# mecanum_car_controller.net
KiCad netlist of a schematic drawn in Altium Designer
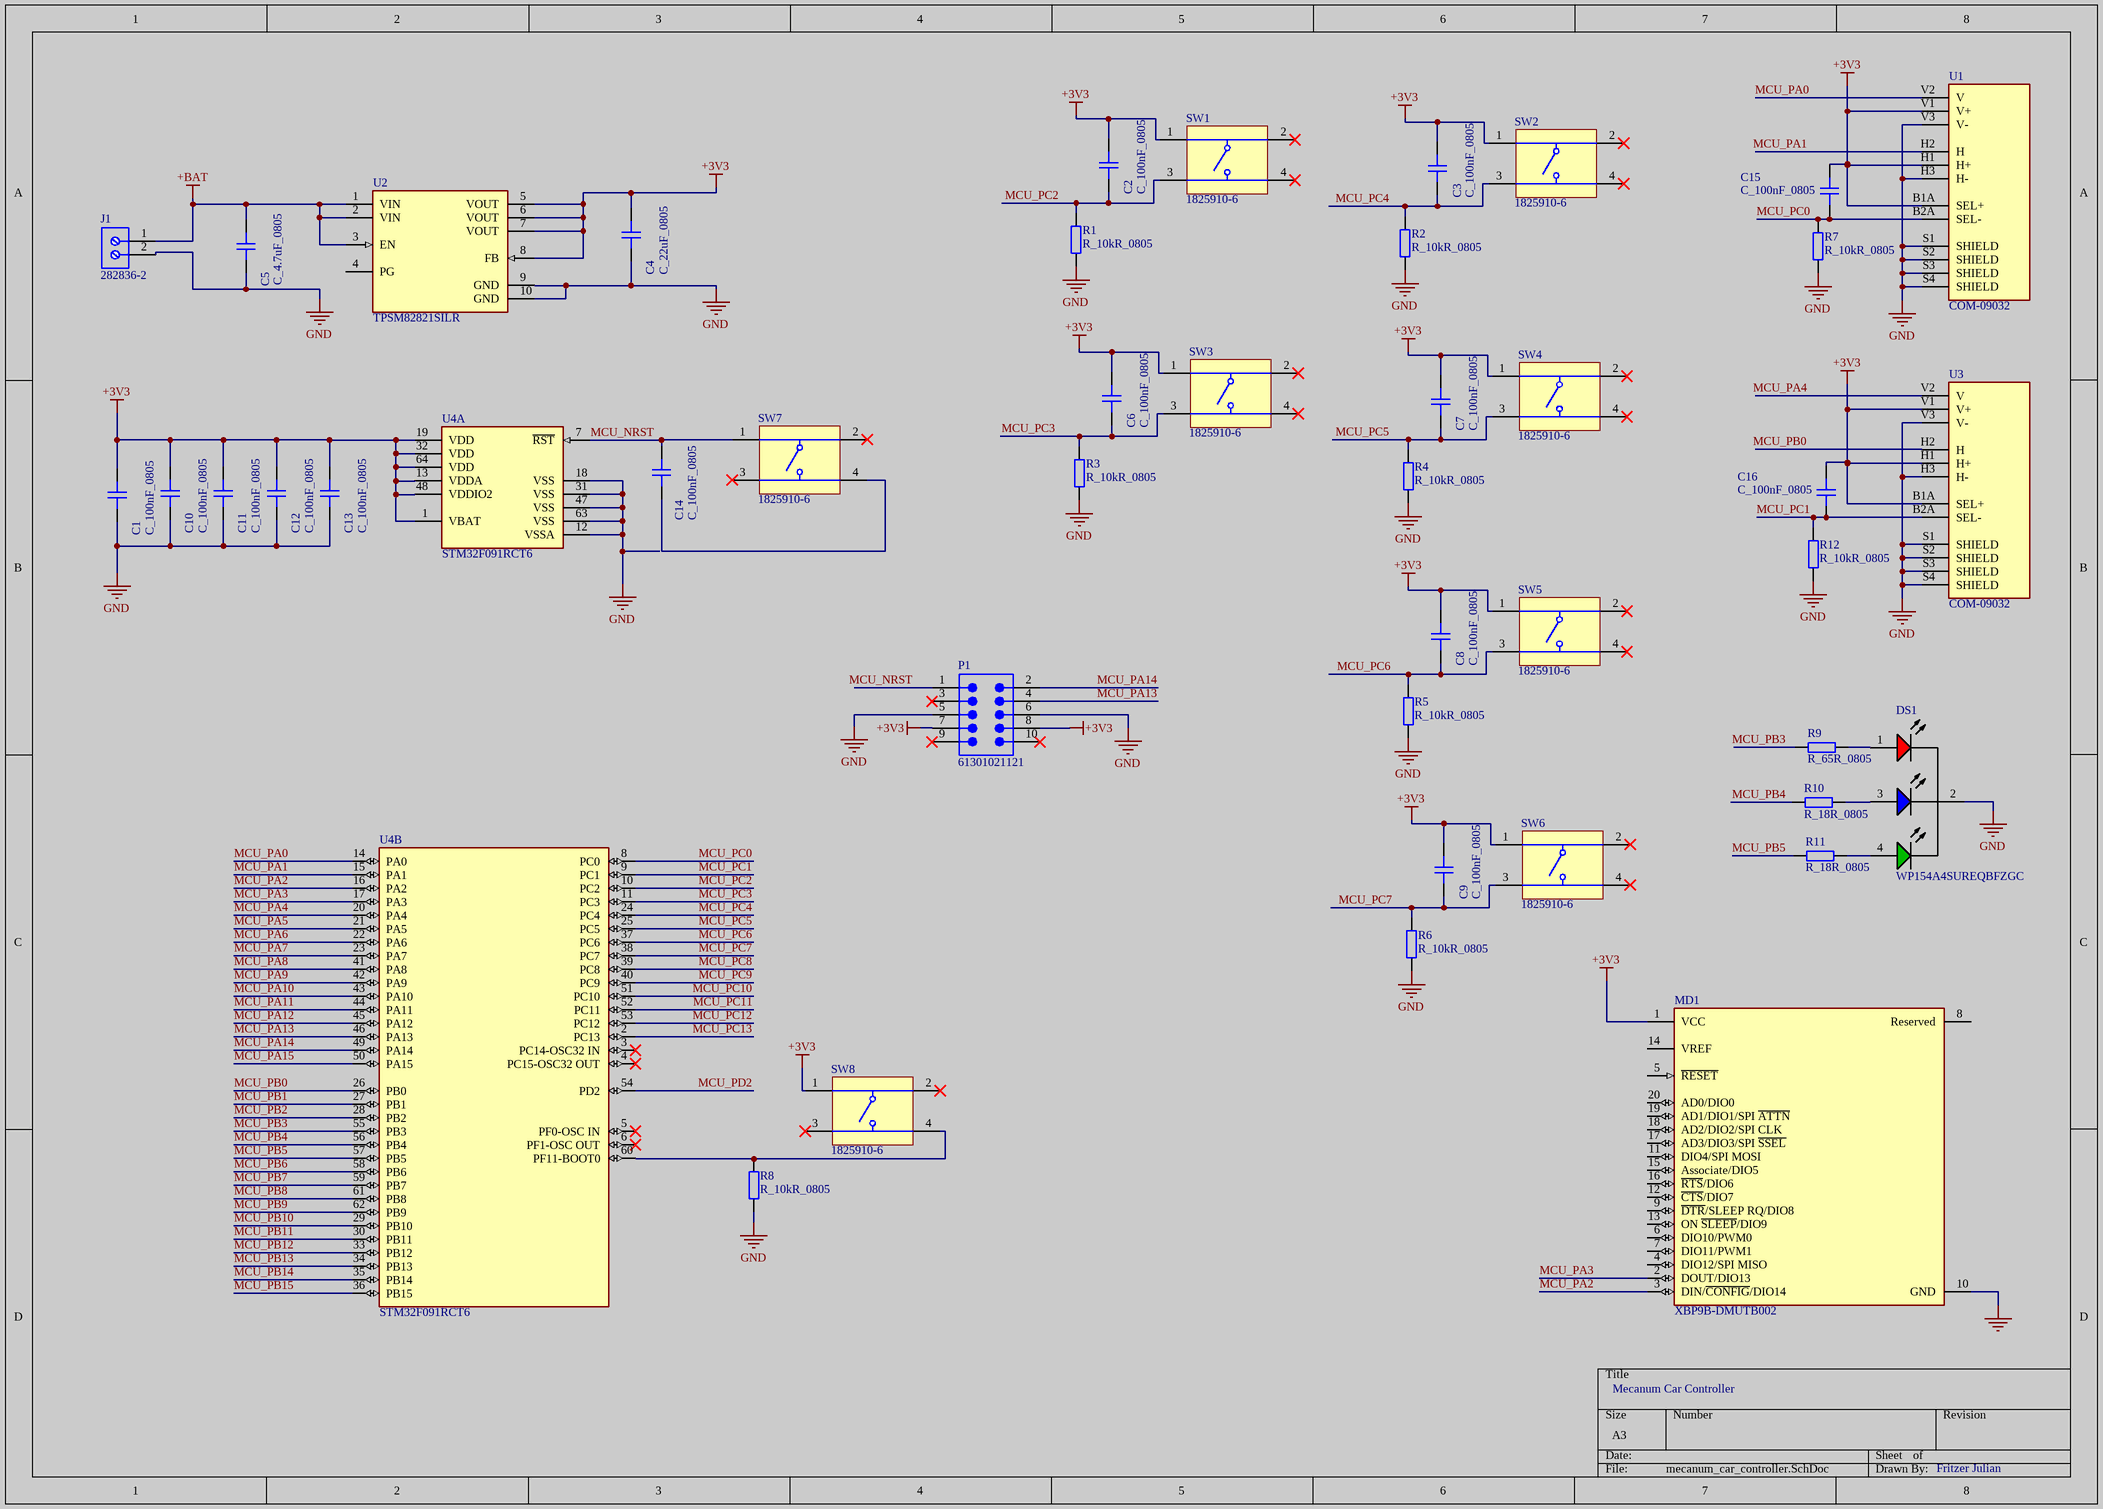
[diagram p0: mecanum_car_controller.SchDoc]

(export (version "E")
  (design (tool "Eeschema 10.0.6"))
  (components
    (comp (ref "C1")
      (value "C_100nF_0805")
      (footprint "CAP_0805")
      (description "Capacitor SMD 0805")
      (libsource (lib "Schematic-Lib-PhilsLab") (part "CAP_0805"))
    )
    (comp (ref "C2")
      (value "C_100nF_0805")
      (footprint "CAP_0805")
      (description "Capacitor SMD 0805")
      (libsource (lib "Schematic-Lib-PhilsLab") (part "CAP_0805"))
    )
    (comp (ref "C3")
      (value "C_100nF_0805")
      (footprint "CAP_0805")
      (description "Capacitor SMD 0805")
      (libsource (lib "Schematic-Lib-PhilsLab") (part "CAP_0805"))
    )
    (comp (ref "C4")
      (value "C_22uF_0805")
      (footprint "CAP_0805")
      (description "Capacitor SMD 0805")
      (libsource (lib "Schematic-Lib-PhilsLab") (part "CAP_0805"))
    )
    (comp (ref "C5")
      (value "C_4.7uF_0805")
      (footprint "CAP_0805")
      (description "Capacitor SMD 0805")
      (libsource (lib "Schematic-Lib-PhilsLab") (part "CAP_0805"))
    )
    (comp (ref "C6")
      (value "C_100nF_0805")
      (footprint "CAP_0805")
      (description "Capacitor SMD 0805")
      (libsource (lib "Schematic-Lib-PhilsLab") (part "CAP_0805"))
    )
    (comp (ref "C7")
      (value "C_100nF_0805")
      (footprint "CAP_0805")
      (description "Capacitor SMD 0805")
      (libsource (lib "Schematic-Lib-PhilsLab") (part "CAP_0805"))
    )
    (comp (ref "C8")
      (value "C_100nF_0805")
      (footprint "CAP_0805")
      (description "Capacitor SMD 0805")
      (libsource (lib "Schematic-Lib-PhilsLab") (part "CAP_0805"))
    )
    (comp (ref "C9")
      (value "C_100nF_0805")
      (footprint "CAP_0805")
      (description "Capacitor SMD 0805")
      (libsource (lib "Schematic-Lib-PhilsLab") (part "CAP_0805"))
    )
    (comp (ref "C10")
      (value "C_100nF_0805")
      (footprint "CAP_0805")
      (description "Capacitor SMD 0805")
      (libsource (lib "Schematic-Lib-PhilsLab") (part "CAP_0805"))
    )
    (comp (ref "C11")
      (value "C_100nF_0805")
      (footprint "CAP_0805")
      (description "Capacitor SMD 0805")
      (libsource (lib "Schematic-Lib-PhilsLab") (part "CAP_0805"))
    )
    (comp (ref "C12")
      (value "C_100nF_0805")
      (footprint "CAP_0805")
      (description "Capacitor SMD 0805")
      (libsource (lib "Schematic-Lib-PhilsLab") (part "CAP_0805"))
    )
    (comp (ref "C13")
      (value "C_100nF_0805")
      (footprint "CAP_0805")
      (description "Capacitor SMD 0805")
      (libsource (lib "Schematic-Lib-PhilsLab") (part "CAP_0805"))
    )
    (comp (ref "C14")
      (value "C_100nF_0805")
      (footprint "CAP_0805")
      (description "Capacitor SMD 0805")
      (libsource (lib "Schematic-Lib-PhilsLab") (part "CAP_0805"))
    )
    (comp (ref "C15")
      (value "C_100nF_0805")
      (footprint "CAP_0805")
      (description "Capacitor SMD 0805")
      (libsource (lib "Schematic-Lib-PhilsLab") (part "CAP_0805"))
    )
    (comp (ref "C16")
      (value "C_100nF_0805")
      (footprint "CAP_0805")
      (description "Capacitor SMD 0805")
      (libsource (lib "Schematic-Lib-PhilsLab") (part "CAP_0805"))
    )
    (comp (ref "DS1")
      (value "WP154A4SUREQBFZGC")
      (footprint "KING-WP154A4SUREQBFZGC_V")
      (description "Full Color LED Lamp, Dominant Wavelength RGB 630 / 525 / 465 nm, -40 to 85 degC, 4-Pin THD, RoHS")
      (fields (field (name "MANUFACTURER") "Kingbright"))
      (libsource (lib "Altium Content Vault") (part "LED-RGB-AKAA-4"))
    )
    (comp (ref "J1")
      (value "282836-2")
      (footprint "TECO-282836-2_V")
      (description "Female Header, Pitch 5 mm, 1 x 2 Position, Height 10 mm, Tail Length 3.5 mm, Rohs, Bulk")
      (fields (field (name "VOLTAGE") "300V") (field (name "MANUFACTURER") "TE Connectivity"))
      (libsource (lib "Altium Content Vault") (part "CN-1P-F-TB2"))
    )
    (comp (ref "MD1")
      (value "XBP9B-DMUTB002")
      (footprint "FP-XBP9B-DMUTB002-MFG")
      (description "RX TXRX MOD ISM < 1GHZ U.FL TH")
      (libsource (lib "Altium Content Vault") (part "053d8e65a610ce00d52093c0e212ca3"))
    )
    (comp (ref "P1")
      (value "61301021121")
      (footprint "61301021121")
      (libsource (lib "Altium Content Vault") (part "Header_Male_2R_10P"))
    )
    (comp (ref "R1")
      (value "R_10kR_0805")
      (footprint "RES_0805")
      (description "Resistor SMD 0805")
      (libsource (lib "Schematic-Lib-PhilsLab") (part "RES_0805"))
    )
    (comp (ref "R2")
      (value "R_10kR_0805")
      (footprint "RES_0805")
      (description "Resistor SMD 0805")
      (libsource (lib "Schematic-Lib-PhilsLab") (part "RES_0805"))
    )
    (comp (ref "R3")
      (value "R_10kR_0805")
      (footprint "RES_0805")
      (description "Resistor SMD 0805")
      (libsource (lib "Schematic-Lib-PhilsLab") (part "RES_0805"))
    )
    (comp (ref "R4")
      (value "R_10kR_0805")
      (footprint "RES_0805")
      (description "Resistor SMD 0805")
      (libsource (lib "Schematic-Lib-PhilsLab") (part "RES_0805"))
    )
    (comp (ref "R5")
      (value "R_10kR_0805")
      (footprint "RES_0805")
      (description "Resistor SMD 0805")
      (libsource (lib "Schematic-Lib-PhilsLab") (part "RES_0805"))
    )
    (comp (ref "R6")
      (value "R_10kR_0805")
      (footprint "RES_0805")
      (description "Resistor SMD 0805")
      (libsource (lib "Schematic-Lib-PhilsLab") (part "RES_0805"))
    )
    (comp (ref "R7")
      (value "R_10kR_0805")
      (footprint "RES_0805")
      (description "Resistor SMD 0805")
      (libsource (lib "Schematic-Lib-PhilsLab") (part "RES_0805"))
    )
    (comp (ref "R8")
      (value "R_10kR_0805")
      (footprint "RES_0805")
      (description "Resistor SMD 0805")
      (libsource (lib "Schematic-Lib-PhilsLab") (part "RES_0805"))
    )
    (comp (ref "R9")
      (value "R_65R_0805")
      (footprint "RES_0805")
      (description "Resistor SMD 0805")
      (libsource (lib "Schematic-Lib-PhilsLab") (part "RES_0805"))
    )
    (comp (ref "R10")
      (value "R_18R_0805")
      (footprint "RES_0805")
      (description "Resistor SMD 0805")
      (libsource (lib "Schematic-Lib-PhilsLab") (part "RES_0805"))
    )
    (comp (ref "R11")
      (value "R_18R_0805")
      (footprint "RES_0805")
      (description "Resistor SMD 0805")
      (libsource (lib "Schematic-Lib-PhilsLab") (part "RES_0805"))
    )
    (comp (ref "R12")
      (value "R_10kR_0805")
      (footprint "RES_0805")
      (description "Resistor SMD 0805")
      (libsource (lib "Schematic-Lib-PhilsLab") (part "RES_0805"))
    )
    (comp (ref "SW1")
      (value "1825910-6")
      (footprint "TECO-1825910-6_V")
      (description "Tact Switch, SPST-NO, 0.05 A, -35 to 85 degC, 4-Pin THD, RoHS, Bulk")
      (fields (field (name "MANUFACTURER") "TE Connectivity"))
      (libsource (lib "Altium Content Vault") (part "SW-SPST-4_A"))
    )
    (comp (ref "SW2")
      (value "1825910-6")
      (footprint "TECO-1825910-6_V")
      (description "Tact Switch, SPST-NO, 0.05 A, -35 to 85 degC, 4-Pin THD, RoHS, Bulk")
      (fields (field (name "MANUFACTURER") "TE Connectivity"))
      (libsource (lib "Altium Content Vault") (part "SW-SPST-4_A"))
    )
    (comp (ref "SW3")
      (value "1825910-6")
      (footprint "TECO-1825910-6_V")
      (description "Tact Switch, SPST-NO, 0.05 A, -35 to 85 degC, 4-Pin THD, RoHS, Bulk")
      (fields (field (name "MANUFACTURER") "TE Connectivity"))
      (libsource (lib "Altium Content Vault") (part "SW-SPST-4_A"))
    )
    (comp (ref "SW4")
      (value "1825910-6")
      (footprint "TECO-1825910-6_V")
      (description "Tact Switch, SPST-NO, 0.05 A, -35 to 85 degC, 4-Pin THD, RoHS, Bulk")
      (fields (field (name "MANUFACTURER") "TE Connectivity"))
      (libsource (lib "Altium Content Vault") (part "SW-SPST-4_A"))
    )
    (comp (ref "SW5")
      (value "1825910-6")
      (footprint "TECO-1825910-6_V")
      (description "Tact Switch, SPST-NO, 0.05 A, -35 to 85 degC, 4-Pin THD, RoHS, Bulk")
      (fields (field (name "MANUFACTURER") "TE Connectivity"))
      (libsource (lib "Altium Content Vault") (part "SW-SPST-4_A"))
    )
    (comp (ref "SW6")
      (value "1825910-6")
      (footprint "TECO-1825910-6_V")
      (description "Tact Switch, SPST-NO, 0.05 A, -35 to 85 degC, 4-Pin THD, RoHS, Bulk")
      (fields (field (name "MANUFACTURER") "TE Connectivity"))
      (libsource (lib "Altium Content Vault") (part "SW-SPST-4_A"))
    )
    (comp (ref "SW7")
      (value "1825910-6")
      (footprint "TECO-1825910-6_V")
      (description "Tact Switch, SPST-NO, 0.05 A, -35 to 85 degC, 4-Pin THD, RoHS, Bulk")
      (fields (field (name "MANUFACTURER") "TE Connectivity"))
      (libsource (lib "Altium Content Vault") (part "SW-SPST-4_A"))
    )
    (comp (ref "SW8")
      (value "1825910-6")
      (footprint "TECO-1825910-6_V")
      (description "Tact Switch, SPST-NO, 0.05 A, -35 to 85 degC, 4-Pin THD, RoHS, Bulk")
      (fields (field (name "MANUFACTURER") "TE Connectivity"))
      (libsource (lib "Altium Content Vault") (part "SW-SPST-4_A"))
    )
    (comp (ref "U1")
      (value "COM-09032")
      (footprint "XDCR_COM-09032")
      (description "Thumb Joystick")
      (libsource (lib "MCI Study") (part "COM-09032"))
    )
    (comp (ref "U2")
      (value "TPSM82821SILR")
      (footprint "FP-SIL0010D-MFG")
      (description "5.5-V INPUT, 1-A STEP-DOWN MODUL")
      (libsource (lib "Altium Content Vault") (part "68384de76e7b35abcf0e6d2c113385e"))
    )
    (comp (ref "U3")
      (value "COM-09032")
      (footprint "XDCR_COM-09032")
      (description "Thumb Joystick")
      (libsource (lib "MCI Study") (part "COM-09032"))
    )
    (comp (ref "U4")
      (value "STM32F091RCT6")
      (footprint "FP-LQFP64-5W-MFG")
      (description "IC MCU 32BIT 256KB FLASH 64LQFP")
      (fields
        (field (name "MANUFACTURER") "STMicroelectronics")
        (field (name "OCTOPART") "https://octopart.com/stm32f091rct6-stmicroelectronics-51988683")
      )
      (libsource (lib "Altium Content Vault") (part "bfbeca3fb2451641a73f006bbf133b6"))
    )
  )
  (nets
    (net (code "1") (name "+3V3") (class "Default")
      (node (ref "C1") (pin "2") (pinfunction "2_2") (pintype "passive"))
      (node (ref "C10") (pin "2") (pinfunction "2_2") (pintype "passive"))
      (node (ref "C11") (pin "2") (pinfunction "2_2") (pintype "passive"))
      (node (ref "C12") (pin "2") (pinfunction "2_2") (pintype "passive"))
      (node (ref "C13") (pin "2") (pinfunction "2_2") (pintype "passive"))
      (node (ref "C15") (pin "2") (pinfunction "2_2") (pintype "passive"))
      (node (ref "C16") (pin "2") (pinfunction "2_2") (pintype "passive"))
      (node (ref "C2") (pin "2") (pinfunction "2_2") (pintype "passive"))
      (node (ref "C3") (pin "2") (pinfunction "2_2") (pintype "passive"))
      (node (ref "C4") (pin "2") (pinfunction "2_2") (pintype "passive"))
      (node (ref "C6") (pin "2") (pinfunction "2_2") (pintype "passive"))
      (node (ref "C7") (pin "2") (pinfunction "2_2") (pintype "passive"))
      (node (ref "C8") (pin "2") (pinfunction "2_2") (pintype "passive"))
      (node (ref "C9") (pin "2") (pinfunction "2_2") (pintype "passive"))
      (node (ref "MD1") (pin "1") (pinfunction "VCC_1") (pintype "power_in"))
      (node (ref "P1") (pin "7") (pinfunction "7_7") (pintype "passive"))
      (node (ref "P1") (pin "8") (pinfunction "8_8") (pintype "passive"))
      (node (ref "SW1") (pin "1") (pinfunction "1_1") (pintype "passive"))
      (node (ref "SW2") (pin "1") (pinfunction "1_1") (pintype "passive"))
      (node (ref "SW3") (pin "1") (pinfunction "1_1") (pintype "passive"))
      (node (ref "SW4") (pin "1") (pinfunction "1_1") (pintype "passive"))
      (node (ref "SW5") (pin "1") (pinfunction "1_1") (pintype "passive"))
      (node (ref "SW6") (pin "1") (pinfunction "1_1") (pintype "passive"))
      (node (ref "SW8") (pin "1") (pinfunction "1_1") (pintype "passive"))
      (node (ref "U1") (pin "B1A") (pinfunction "SEL+_B1A") (pintype "passive"))
      (node (ref "U1") (pin "H1") (pinfunction "H+_H1") (pintype "passive"))
      (node (ref "U1") (pin "V1") (pinfunction "V+_V1") (pintype "passive"))
      (node (ref "U2") (pin "5") (pinfunction "VOUT_5") (pintype "passive"))
      (node (ref "U2") (pin "6") (pinfunction "VOUT_6") (pintype "passive"))
      (node (ref "U2") (pin "7") (pinfunction "VOUT_7") (pintype "passive"))
      (node (ref "U2") (pin "8") (pinfunction "FB_8") (pintype "input"))
      (node (ref "U3") (pin "B1A") (pinfunction "SEL+_B1A") (pintype "passive"))
      (node (ref "U3") (pin "H1") (pinfunction "H+_H1") (pintype "passive"))
      (node (ref "U3") (pin "V1") (pinfunction "V+_V1") (pintype "passive"))
      (node (ref "U4") (pin "1") (pinfunction "VBAT_1") (pintype "power_in"))
      (node (ref "U4") (pin "13") (pinfunction "VDDA_13") (pintype "power_in"))
      (node (ref "U4") (pin "19") (pinfunction "VDD_19") (pintype "power_in"))
      (node (ref "U4") (pin "32") (pinfunction "VDD_32") (pintype "power_in"))
      (node (ref "U4") (pin "48") (pinfunction "VDDIO2_48") (pintype "power_in"))
      (node (ref "U4") (pin "64") (pinfunction "VDD_64") (pintype "power_in"))
    )
    (net (code "2") (name "+BAT") (class "Default")
      (node (ref "C5") (pin "2") (pinfunction "2_2") (pintype "passive"))
      (node (ref "J1") (pin "1") (pinfunction "1_1") (pintype "passive"))
      (node (ref "U2") (pin "1") (pinfunction "VIN_1") (pintype "power_in"))
      (node (ref "U2") (pin "2") (pinfunction "VIN_2") (pintype "power_in"))
      (node (ref "U2") (pin "3") (pinfunction "EN_3") (pintype "input"))
    )
    (net (code "3") (name "/MCU_NRST") (class "Default")
      (node (ref "C14") (pin "2") (pinfunction "2_2") (pintype "passive"))
      (node (ref "P1") (pin "1") (pinfunction "1_1") (pintype "passive"))
      (node (ref "SW7") (pin "1") (pinfunction "1_1") (pintype "passive"))
      (node (ref "U4") (pin "7") (pinfunction "~{RST}_7") (pintype "input"))
    )
    (net (code "4") (name "/MCU_PA0") (class "Default")
      (node (ref "U1") (pin "V2") (pinfunction "V_V2") (pintype "passive"))
      (node (ref "U4") (pin "14") (pinfunction "PA0_14") (pintype "bidirectional"))
    )
    (net (code "5") (name "/MCU_PA1") (class "Default")
      (node (ref "U1") (pin "H2") (pinfunction "H_H2") (pintype "passive"))
      (node (ref "U4") (pin "15") (pinfunction "PA1_15") (pintype "bidirectional"))
    )
    (net (code "6") (name "/MCU_PA2") (class "Default")
      (node (ref "MD1") (pin "3") (pinfunction "DIN/~{CONFIG}/DIO14_3") (pintype "bidirectional"))
      (node (ref "U4") (pin "16") (pinfunction "PA2_16") (pintype "bidirectional"))
    )
    (net (code "7") (name "/MCU_PA3") (class "Default")
      (node (ref "MD1") (pin "2") (pinfunction "DOUT/DIO13_2") (pintype "bidirectional"))
      (node (ref "U4") (pin "17") (pinfunction "PA3_17") (pintype "bidirectional"))
    )
    (net (code "8") (name "/MCU_PA4") (class "Default")
      (node (ref "U3") (pin "V2") (pinfunction "V_V2") (pintype "passive"))
      (node (ref "U4") (pin "20") (pinfunction "PA4_20") (pintype "bidirectional"))
    )
    (net (code "9") (name "/MCU_PA5") (class "Default")
      (node (ref "U4") (pin "21") (pinfunction "PA5_21") (pintype "bidirectional"))
    )
    (net (code "10") (name "/MCU_PA6") (class "Default")
      (node (ref "U4") (pin "22") (pinfunction "PA6_22") (pintype "bidirectional"))
    )
    (net (code "11") (name "/MCU_PA7") (class "Default")
      (node (ref "U4") (pin "23") (pinfunction "PA7_23") (pintype "bidirectional"))
    )
    (net (code "12") (name "/MCU_PA8") (class "Default")
      (node (ref "U4") (pin "41") (pinfunction "PA8_41") (pintype "bidirectional"))
    )
    (net (code "13") (name "/MCU_PA9") (class "Default")
      (node (ref "U4") (pin "42") (pinfunction "PA9_42") (pintype "bidirectional"))
    )
    (net (code "14") (name "/MCU_PA10") (class "Default")
      (node (ref "U4") (pin "43") (pinfunction "PA10_43") (pintype "bidirectional"))
    )
    (net (code "15") (name "/MCU_PA11") (class "Default")
      (node (ref "U4") (pin "44") (pinfunction "PA11_44") (pintype "bidirectional"))
    )
    (net (code "16") (name "/MCU_PA12") (class "Default")
      (node (ref "U4") (pin "45") (pinfunction "PA12_45") (pintype "bidirectional"))
    )
    (net (code "17") (name "/MCU_PA13") (class "Default")
      (node (ref "P1") (pin "4") (pinfunction "4_4") (pintype "passive"))
      (node (ref "U4") (pin "46") (pinfunction "PA13_46") (pintype "bidirectional"))
    )
    (net (code "18") (name "/MCU_PA14") (class "Default")
      (node (ref "P1") (pin "2") (pinfunction "2_2") (pintype "passive"))
      (node (ref "U4") (pin "49") (pinfunction "PA14_49") (pintype "bidirectional"))
    )
    (net (code "19") (name "/MCU_PA15") (class "Default")
      (node (ref "U4") (pin "50") (pinfunction "PA15_50") (pintype "bidirectional"))
    )
    (net (code "20") (name "/MCU_PB0") (class "Default")
      (node (ref "U3") (pin "H2") (pinfunction "H_H2") (pintype "passive"))
      (node (ref "U4") (pin "26") (pinfunction "PB0_26") (pintype "bidirectional"))
    )
    (net (code "21") (name "/MCU_PB1") (class "Default")
      (node (ref "U4") (pin "27") (pinfunction "PB1_27") (pintype "bidirectional"))
    )
    (net (code "22") (name "/MCU_PB2") (class "Default")
      (node (ref "U4") (pin "28") (pinfunction "PB2_28") (pintype "bidirectional"))
    )
    (net (code "23") (name "/MCU_PB3") (class "Default")
      (node (ref "R9") (pin "2") (pinfunction "2_2") (pintype "passive"))
      (node (ref "U4") (pin "55") (pinfunction "PB3_55") (pintype "bidirectional"))
    )
    (net (code "24") (name "/MCU_PB4") (class "Default")
      (node (ref "R10") (pin "2") (pinfunction "2_2") (pintype "passive"))
      (node (ref "U4") (pin "56") (pinfunction "PB4_56") (pintype "bidirectional"))
    )
    (net (code "25") (name "/MCU_PB5") (class "Default")
      (node (ref "R11") (pin "2") (pinfunction "2_2") (pintype "passive"))
      (node (ref "U4") (pin "57") (pinfunction "PB5_57") (pintype "bidirectional"))
    )
    (net (code "26") (name "/MCU_PB6") (class "Default")
      (node (ref "U4") (pin "58") (pinfunction "PB6_58") (pintype "bidirectional"))
    )
    (net (code "27") (name "/MCU_PB7") (class "Default")
      (node (ref "U4") (pin "59") (pinfunction "PB7_59") (pintype "bidirectional"))
    )
    (net (code "28") (name "/MCU_PB8") (class "Default")
      (node (ref "U4") (pin "61") (pinfunction "PB8_61") (pintype "bidirectional"))
    )
    (net (code "29") (name "/MCU_PB9") (class "Default")
      (node (ref "U4") (pin "62") (pinfunction "PB9_62") (pintype "bidirectional"))
    )
    (net (code "30") (name "/MCU_PB10") (class "Default")
      (node (ref "U4") (pin "29") (pinfunction "PB10_29") (pintype "bidirectional"))
    )
    (net (code "31") (name "/MCU_PB11") (class "Default")
      (node (ref "U4") (pin "30") (pinfunction "PB11_30") (pintype "bidirectional"))
    )
    (net (code "32") (name "/MCU_PB12") (class "Default")
      (node (ref "U4") (pin "33") (pinfunction "PB12_33") (pintype "bidirectional"))
    )
    (net (code "33") (name "/MCU_PB13") (class "Default")
      (node (ref "U4") (pin "34") (pinfunction "PB13_34") (pintype "bidirectional"))
    )
    (net (code "34") (name "/MCU_PB14") (class "Default")
      (node (ref "U4") (pin "35") (pinfunction "PB14_35") (pintype "bidirectional"))
    )
    (net (code "35") (name "/MCU_PB15") (class "Default")
      (node (ref "U4") (pin "36") (pinfunction "PB15_36") (pintype "bidirectional"))
    )
    (net (code "36") (name "/MCU_PC0") (class "Default")
      (node (ref "C15") (pin "1") (pinfunction "1_1") (pintype "passive"))
      (node (ref "R7") (pin "1") (pinfunction "1_1") (pintype "passive"))
      (node (ref "U1") (pin "B2A") (pinfunction "SEL-_B2A") (pintype "passive"))
      (node (ref "U4") (pin "8") (pinfunction "PC0_8") (pintype "bidirectional"))
    )
    (net (code "37") (name "/MCU_PC1") (class "Default")
      (node (ref "C16") (pin "1") (pinfunction "1_1") (pintype "passive"))
      (node (ref "R12") (pin "1") (pinfunction "1_1") (pintype "passive"))
      (node (ref "U3") (pin "B2A") (pinfunction "SEL-_B2A") (pintype "passive"))
      (node (ref "U4") (pin "9") (pinfunction "PC1_9") (pintype "bidirectional"))
    )
    (net (code "38") (name "/MCU_PC2") (class "Default")
      (node (ref "C2") (pin "1") (pinfunction "1_1") (pintype "passive"))
      (node (ref "R1") (pin "1") (pinfunction "1_1") (pintype "passive"))
      (node (ref "SW1") (pin "3") (pinfunction "3_3") (pintype "passive"))
      (node (ref "U4") (pin "10") (pinfunction "PC2_10") (pintype "bidirectional"))
    )
    (net (code "39") (name "/MCU_PC3") (class "Default")
      (node (ref "C6") (pin "1") (pinfunction "1_1") (pintype "passive"))
      (node (ref "R3") (pin "1") (pinfunction "1_1") (pintype "passive"))
      (node (ref "SW3") (pin "3") (pinfunction "3_3") (pintype "passive"))
      (node (ref "U4") (pin "11") (pinfunction "PC3_11") (pintype "bidirectional"))
    )
    (net (code "40") (name "/MCU_PC4") (class "Default")
      (node (ref "C3") (pin "1") (pinfunction "1_1") (pintype "passive"))
      (node (ref "R2") (pin "1") (pinfunction "1_1") (pintype "passive"))
      (node (ref "SW2") (pin "3") (pinfunction "3_3") (pintype "passive"))
      (node (ref "U4") (pin "24") (pinfunction "PC4_24") (pintype "bidirectional"))
    )
    (net (code "41") (name "/MCU_PC5") (class "Default")
      (node (ref "C7") (pin "1") (pinfunction "1_1") (pintype "passive"))
      (node (ref "R4") (pin "1") (pinfunction "1_1") (pintype "passive"))
      (node (ref "SW4") (pin "3") (pinfunction "3_3") (pintype "passive"))
      (node (ref "U4") (pin "25") (pinfunction "PC5_25") (pintype "bidirectional"))
    )
    (net (code "42") (name "/MCU_PC6") (class "Default")
      (node (ref "C8") (pin "1") (pinfunction "1_1") (pintype "passive"))
      (node (ref "R5") (pin "1") (pinfunction "1_1") (pintype "passive"))
      (node (ref "SW5") (pin "3") (pinfunction "3_3") (pintype "passive"))
      (node (ref "U4") (pin "37") (pinfunction "PC6_37") (pintype "bidirectional"))
    )
    (net (code "43") (name "/MCU_PC7") (class "Default")
      (node (ref "C9") (pin "1") (pinfunction "1_1") (pintype "passive"))
      (node (ref "R6") (pin "1") (pinfunction "1_1") (pintype "passive"))
      (node (ref "SW6") (pin "3") (pinfunction "3_3") (pintype "passive"))
      (node (ref "U4") (pin "38") (pinfunction "PC7_38") (pintype "bidirectional"))
    )
    (net (code "44") (name "/MCU_PC8") (class "Default")
      (node (ref "U4") (pin "39") (pinfunction "PC8_39") (pintype "bidirectional"))
    )
    (net (code "45") (name "/MCU_PC9") (class "Default")
      (node (ref "U4") (pin "40") (pinfunction "PC9_40") (pintype "bidirectional"))
    )
    (net (code "46") (name "/MCU_PC10") (class "Default")
      (node (ref "U4") (pin "51") (pinfunction "PC10_51") (pintype "bidirectional"))
    )
    (net (code "47") (name "/MCU_PC11") (class "Default")
      (node (ref "U4") (pin "52") (pinfunction "PC11_52") (pintype "bidirectional"))
    )
    (net (code "48") (name "/MCU_PC12") (class "Default")
      (node (ref "U4") (pin "53") (pinfunction "PC12_53") (pintype "bidirectional"))
    )
    (net (code "49") (name "/MCU_PC13") (class "Default")
      (node (ref "U4") (pin "2") (pinfunction "PC13_2") (pintype "bidirectional"))
    )
    (net (code "50") (name "/MCU_PD2") (class "Default")
      (node (ref "U4") (pin "54") (pinfunction "PD2_54") (pintype "bidirectional"))
    )
    (net (code "51") (name "<NO NET>") (class "Default")
      (node (ref "MD1") (pin "10") (pinfunction "GND_10") (pintype "power_in"))
    )
    (net (code "52") (name "GND") (class "Default")
      (node (ref "C1") (pin "1") (pinfunction "1_1") (pintype "passive"))
      (node (ref "C10") (pin "1") (pinfunction "1_1") (pintype "passive"))
      (node (ref "C11") (pin "1") (pinfunction "1_1") (pintype "passive"))
      (node (ref "C12") (pin "1") (pinfunction "1_1") (pintype "passive"))
      (node (ref "C13") (pin "1") (pinfunction "1_1") (pintype "passive"))
      (node (ref "C4") (pin "1") (pinfunction "1_1") (pintype "passive"))
      (node (ref "C5") (pin "1") (pinfunction "1_1") (pintype "passive"))
      (node (ref "DS1") (pin "2") (pinfunction "CATHODE_2") (pintype "passive"))
      (node (ref "J1") (pin "2") (pinfunction "2_2") (pintype "passive"))
      (node (ref "P1") (pin "5") (pinfunction "5_5") (pintype "passive"))
      (node (ref "P1") (pin "6") (pinfunction "6_6") (pintype "passive"))
      (node (ref "R1") (pin "2") (pinfunction "2_2") (pintype "passive"))
      (node (ref "R12") (pin "2") (pinfunction "2_2") (pintype "passive"))
      (node (ref "R2") (pin "2") (pinfunction "2_2") (pintype "passive"))
      (node (ref "R3") (pin "2") (pinfunction "2_2") (pintype "passive"))
      (node (ref "R4") (pin "2") (pinfunction "2_2") (pintype "passive"))
      (node (ref "R5") (pin "2") (pinfunction "2_2") (pintype "passive"))
      (node (ref "R6") (pin "2") (pinfunction "2_2") (pintype "passive"))
      (node (ref "R7") (pin "2") (pinfunction "2_2") (pintype "passive"))
      (node (ref "R8") (pin "2") (pinfunction "2_2") (pintype "passive"))
      (node (ref "U1") (pin "H3") (pinfunction "H-_H3") (pintype "passive"))
      (node (ref "U1") (pin "S1") (pinfunction "SHIELD_S1") (pintype "passive"))
      (node (ref "U1") (pin "S2") (pinfunction "SHIELD_S2") (pintype "passive"))
      (node (ref "U1") (pin "S3") (pinfunction "SHIELD_S3") (pintype "passive"))
      (node (ref "U1") (pin "S4") (pinfunction "SHIELD_S4") (pintype "passive"))
      (node (ref "U1") (pin "V3") (pinfunction "V-_V3") (pintype "passive"))
      (node (ref "U2") (pin "10") (pinfunction "GND_10") (pintype "power_in"))
      (node (ref "U2") (pin "9") (pinfunction "GND_9") (pintype "power_in"))
      (node (ref "U3") (pin "H3") (pinfunction "H-_H3") (pintype "passive"))
      (node (ref "U3") (pin "S1") (pinfunction "SHIELD_S1") (pintype "passive"))
      (node (ref "U3") (pin "S2") (pinfunction "SHIELD_S2") (pintype "passive"))
      (node (ref "U3") (pin "S3") (pinfunction "SHIELD_S3") (pintype "passive"))
      (node (ref "U3") (pin "S4") (pinfunction "SHIELD_S4") (pintype "passive"))
      (node (ref "U3") (pin "V3") (pinfunction "V-_V3") (pintype "passive"))
      (node (ref "U4") (pin "12") (pinfunction "VSSA_12") (pintype "power_in"))
      (node (ref "U4") (pin "18") (pinfunction "VSS_18") (pintype "power_in"))
      (node (ref "U4") (pin "31") (pinfunction "VSS_31") (pintype "power_in"))
      (node (ref "U4") (pin "47") (pinfunction "VSS_47") (pintype "power_in"))
      (node (ref "U4") (pin "63") (pinfunction "VSS_63") (pintype "power_in"))
    )
    (net (code "53") (name "Net-(C14-Pad1)") (class "Default")
      (node (ref "C14") (pin "1") (pinfunction "1_1") (pintype "passive"))
      (node (ref "SW7") (pin "4") (pinfunction "4_4") (pintype "passive"))
    )
    (net (code "54") (name "Net-(DS1-BLUE)") (class "Default")
      (node (ref "DS1") (pin "3") (pinfunction "BLUE_3") (pintype "passive"))
      (node (ref "R10") (pin "1") (pinfunction "1_1") (pintype "passive"))
    )
    (net (code "55") (name "Net-(DS1-GREEN)") (class "Default")
      (node (ref "DS1") (pin "4") (pinfunction "GREEN_4") (pintype "passive"))
      (node (ref "R11") (pin "1") (pinfunction "1_1") (pintype "passive"))
    )
    (net (code "56") (name "Net-(DS1-RED)") (class "Default")
      (node (ref "DS1") (pin "1") (pinfunction "RED_1") (pintype "passive"))
      (node (ref "R9") (pin "1") (pinfunction "1_1") (pintype "passive"))
    )
    (net (code "57") (name "Net-(U4B-PF11-BOOT0)") (class "Default")
      (node (ref "R8") (pin "1") (pinfunction "1_1") (pintype "passive"))
      (node (ref "SW8") (pin "4") (pinfunction "4_4") (pintype "passive"))
      (node (ref "U4") (pin "60") (pinfunction "PF11-BOOT0_60") (pintype "bidirectional"))
    )
    (net (code "58") (name "unconnected-(MD1-AD0{slash}DIO0-Pad20)") (class "Default")
      (node (ref "MD1") (pin "20") (pinfunction "AD0/DIO0_20") (pintype "bidirectional"))
    )
    (net (code "59") (name "unconnected-(MD1-AD1{slash}DIO1{slash}SPI_~{ATTN}-Pad19)") (class "Default")
      (node (ref "MD1") (pin "19") (pinfunction "AD1/DIO1/SPI_~{ATTN}_19") (pintype "bidirectional"))
    )
    (net (code "60") (name "unconnected-(MD1-AD2{slash}DIO2{slash}SPI_CLK-Pad18)") (class "Default")
      (node (ref "MD1") (pin "18") (pinfunction "AD2/DIO2/SPI_CLK_18") (pintype "bidirectional"))
    )
    (net (code "61") (name "unconnected-(MD1-AD3{slash}DIO3{slash}SPI_~{SSEL}-Pad17)") (class "Default")
      (node (ref "MD1") (pin "17") (pinfunction "AD3/DIO3/SPI_~{SSEL}_17") (pintype "bidirectional"))
    )
    (net (code "62") (name "unconnected-(MD1-Associate{slash}DIO5-Pad15)") (class "Default")
      (node (ref "MD1") (pin "15") (pinfunction "Associate/DIO5_15") (pintype "bidirectional"))
    )
    (net (code "63") (name "unconnected-(MD1-DIO4{slash}SPI_MOSI-Pad11)") (class "Default")
      (node (ref "MD1") (pin "11") (pinfunction "DIO4/SPI_MOSI_11") (pintype "bidirectional"))
    )
    (net (code "64") (name "unconnected-(MD1-DIO10{slash}PWM0-Pad6)") (class "Default")
      (node (ref "MD1") (pin "6") (pinfunction "DIO10/PWM0_6") (pintype "bidirectional"))
    )
    (net (code "65") (name "unconnected-(MD1-DIO11{slash}PWM1-Pad7)") (class "Default")
      (node (ref "MD1") (pin "7") (pinfunction "DIO11/PWM1_7") (pintype "bidirectional"))
    )
    (net (code "66") (name "unconnected-(MD1-DIO12{slash}SPI_MISO-Pad4)") (class "Default")
      (node (ref "MD1") (pin "4") (pinfunction "DIO12/SPI_MISO_4") (pintype "bidirectional"))
    )
    (net (code "67") (name "unconnected-(MD1-ON_~{SLEEP}{slash}DIO9-Pad13)") (class "Default")
      (node (ref "MD1") (pin "13") (pinfunction "ON_~{SLEEP}/DIO9_13") (pintype "bidirectional"))
    )
    (net (code "68") (name "unconnected-(MD1-Reserved-Pad8)") (class "Default")
      (node (ref "MD1") (pin "8") (pinfunction "Reserved_8") (pintype "passive"))
    )
    (net (code "69") (name "unconnected-(MD1-VREF-Pad14)") (class "Default")
      (node (ref "MD1") (pin "14") (pinfunction "VREF_14") (pintype "passive"))
    )
    (net (code "70") (name "unconnected-(MD1-~{CTS}{slash}DIO7-Pad12)") (class "Default")
      (node (ref "MD1") (pin "12") (pinfunction "~{CTS}/DIO7_12") (pintype "bidirectional"))
    )
    (net (code "71") (name "unconnected-(MD1-~{DTR}{slash}SLEEP_RQ{slash}DIO8-Pad9)") (class "Default")
      (node (ref "MD1") (pin "9") (pinfunction "~{DTR}/SLEEP_RQ/DIO8_9") (pintype "bidirectional"))
    )
    (net (code "72") (name "unconnected-(MD1-~{RESET}-Pad5)") (class "Default")
      (node (ref "MD1") (pin "5") (pinfunction "~{RESET}_5") (pintype "input"))
    )
    (net (code "73") (name "unconnected-(MD1-~{RTS}{slash}DIO6-Pad16)") (class "Default")
      (node (ref "MD1") (pin "16") (pinfunction "~{RTS}/DIO6_16") (pintype "bidirectional"))
    )
    (net (code "74") (name "unconnected-(P1-Pad3)") (class "Default")
      (node (ref "P1") (pin "3") (pinfunction "3_3") (pintype "passive+no_connect"))
    )
    (net (code "75") (name "unconnected-(P1-Pad9)") (class "Default")
      (node (ref "P1") (pin "9") (pinfunction "9_9") (pintype "passive+no_connect"))
    )
    (net (code "76") (name "unconnected-(P1-Pad10)") (class "Default")
      (node (ref "P1") (pin "10") (pinfunction "10_10") (pintype "passive+no_connect"))
    )
    (net (code "77") (name "unconnected-(SW1-Pad2)") (class "Default")
      (node (ref "SW1") (pin "2") (pinfunction "2_2") (pintype "passive+no_connect"))
    )
    (net (code "78") (name "unconnected-(SW1-Pad4)") (class "Default")
      (node (ref "SW1") (pin "4") (pinfunction "4_4") (pintype "passive+no_connect"))
    )
    (net (code "79") (name "unconnected-(SW2-Pad2)") (class "Default")
      (node (ref "SW2") (pin "2") (pinfunction "2_2") (pintype "passive+no_connect"))
    )
    (net (code "80") (name "unconnected-(SW2-Pad4)") (class "Default")
      (node (ref "SW2") (pin "4") (pinfunction "4_4") (pintype "passive+no_connect"))
    )
    (net (code "81") (name "unconnected-(SW3-Pad2)") (class "Default")
      (node (ref "SW3") (pin "2") (pinfunction "2_2") (pintype "passive+no_connect"))
    )
    (net (code "82") (name "unconnected-(SW3-Pad4)") (class "Default")
      (node (ref "SW3") (pin "4") (pinfunction "4_4") (pintype "passive+no_connect"))
    )
    (net (code "83") (name "unconnected-(SW4-Pad2)") (class "Default")
      (node (ref "SW4") (pin "2") (pinfunction "2_2") (pintype "passive+no_connect"))
    )
    (net (code "84") (name "unconnected-(SW4-Pad4)") (class "Default")
      (node (ref "SW4") (pin "4") (pinfunction "4_4") (pintype "passive+no_connect"))
    )
    (net (code "85") (name "unconnected-(SW5-Pad2)") (class "Default")
      (node (ref "SW5") (pin "2") (pinfunction "2_2") (pintype "passive+no_connect"))
    )
    (net (code "86") (name "unconnected-(SW5-Pad4)") (class "Default")
      (node (ref "SW5") (pin "4") (pinfunction "4_4") (pintype "passive+no_connect"))
    )
    (net (code "87") (name "unconnected-(SW6-Pad2)") (class "Default")
      (node (ref "SW6") (pin "2") (pinfunction "2_2") (pintype "passive+no_connect"))
    )
    (net (code "88") (name "unconnected-(SW6-Pad4)") (class "Default")
      (node (ref "SW6") (pin "4") (pinfunction "4_4") (pintype "passive+no_connect"))
    )
    (net (code "89") (name "unconnected-(SW7-Pad2)") (class "Default")
      (node (ref "SW7") (pin "2") (pinfunction "2_2") (pintype "passive+no_connect"))
    )
    (net (code "90") (name "unconnected-(SW7-Pad3)") (class "Default")
      (node (ref "SW7") (pin "3") (pinfunction "3_3") (pintype "passive+no_connect"))
    )
    (net (code "91") (name "unconnected-(SW8-Pad2)") (class "Default")
      (node (ref "SW8") (pin "2") (pinfunction "2_2") (pintype "passive+no_connect"))
    )
    (net (code "92") (name "unconnected-(SW8-Pad3)") (class "Default")
      (node (ref "SW8") (pin "3") (pinfunction "3_3") (pintype "passive+no_connect"))
    )
    (net (code "93") (name "unconnected-(U2-PG-Pad4)") (class "Default")
      (node (ref "U2") (pin "4") (pinfunction "PG_4") (pintype "open_collector"))
    )
    (net (code "94") (name "unconnected-(U4B-PC14-OSC32_IN-Pad3)") (class "Default")
      (node (ref "U4") (pin "3") (pinfunction "PC14-OSC32_IN_3") (pintype "bidirectional+no_connect"))
    )
    (net (code "95") (name "unconnected-(U4B-PC15-OSC32_OUT-Pad4)") (class "Default")
      (node (ref "U4") (pin "4") (pinfunction "PC15-OSC32_OUT_4") (pintype "bidirectional+no_connect"))
    )
    (net (code "96") (name "unconnected-(U4B-PF0-OSC_IN-Pad5)") (class "Default")
      (node (ref "U4") (pin "5") (pinfunction "PF0-OSC_IN_5") (pintype "bidirectional+no_connect"))
    )
    (net (code "97") (name "unconnected-(U4B-PF1-OSC_OUT-Pad6)") (class "Default")
      (node (ref "U4") (pin "6") (pinfunction "PF1-OSC_OUT_6") (pintype "bidirectional+no_connect"))
    )
  )
)
